# NSE2020_1.net
KiCad netlist of a schematic drawn in EAGLE
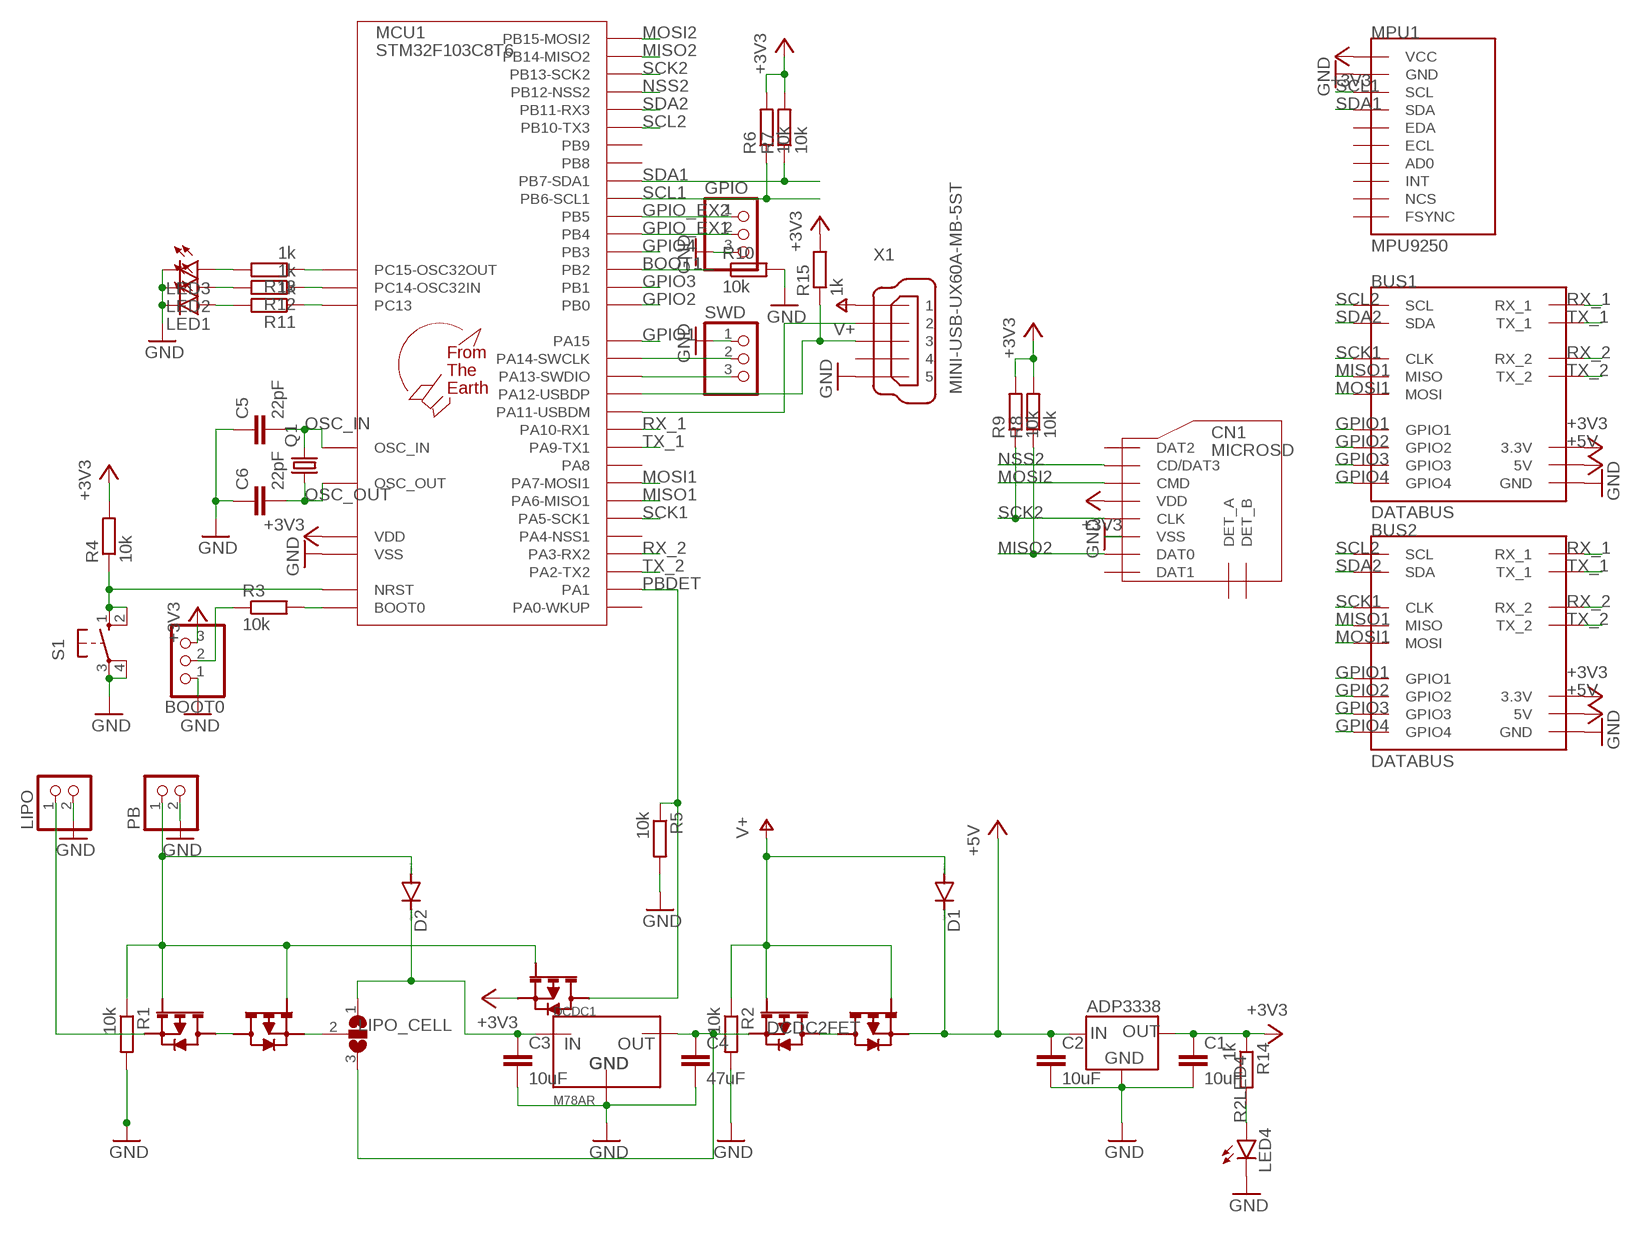
[diagram p0: schematic, sheet 1]

(export (version "E")
  (design (tool "Eeschema 10.0.6"))
  (components
    (comp (ref "BOOT0")
      (value "PINHD-1X3")
      (footprint "eagle-import:1X03")
      (libsource (lib "eagle-import") (part "PINHD-1X3"))
    )
    (comp (ref "BUS1")
      (value "DATABUS")
      (footprint "eagle-import:8X2")
      (libsource (lib "eagle-import") (part "DATABUS"))
    )
    (comp (ref "BUS2")
      (value "DATABUS")
      (footprint "eagle-import:8X2")
      (libsource (lib "eagle-import") (part "DATABUS"))
    )
    (comp (ref "C1")
      (value "10uF")
      (footprint "eagle-import:C2012")
      (libsource (lib "eagle-import") (part "C-EUC2012"))
    )
    (comp (ref "C2")
      (value "10uF")
      (footprint "eagle-import:C2012")
      (libsource (lib "eagle-import") (part "C-EUC2012"))
    )
    (comp (ref "C3")
      (value "10uF")
      (footprint "eagle-import:C2012")
      (libsource (lib "eagle-import") (part "C-EUC2012"))
    )
    (comp (ref "C4")
      (value "47uF")
      (footprint "eagle-import:C2012")
      (libsource (lib "eagle-import") (part "C-EUC2012"))
    )
    (comp (ref "C5")
      (value "22pF")
      (footprint "eagle-import:C2012")
      (libsource (lib "eagle-import") (part "C-EUC2012"))
    )
    (comp (ref "C6")
      (value "22pF")
      (footprint "eagle-import:C2012")
      (libsource (lib "eagle-import") (part "C-EUC2012"))
    )
    (comp (ref "CN1")
      (value "MICROSD")
      (footprint "eagle-import:DM3AT")
      (libsource (lib "eagle-import") (part "MICROSD"))
    )
    (comp (ref "D1")
      (value "DIODE-SOD123")
      (footprint "eagle-import:SOD123")
      (libsource (lib "eagle-import") (part "DIODE-SOD123"))
    )
    (comp (ref "D2")
      (value "DIODE-SOD123")
      (footprint "eagle-import:SOD123")
      (libsource (lib "eagle-import") (part "DIODE-SOD123"))
    )
    (comp (ref "DCDC1")
      (value "M78AR")
      (footprint "eagle-import:M78AR")
      (libsource (lib "eagle-import") (part "M78AR"))
    )
    (comp (ref "FET1")
      (value "2SJ681")
      (footprint "eagle-import:2SJ681")
      (libsource (lib "eagle-import") (part "2SJ681"))
    )
    (comp (ref "FET2")
      (value "2SJ681")
      (footprint "eagle-import:2SJ681")
      (libsource (lib "eagle-import") (part "2SJ681"))
    )
    (comp (ref "FET3")
      (value "2SJ681")
      (footprint "eagle-import:2SJ681")
      (libsource (lib "eagle-import") (part "2SJ681"))
    )
    (comp (ref "FET4")
      (value "2SJ681")
      (footprint "eagle-import:2SJ681")
      (libsource (lib "eagle-import") (part "2SJ681"))
    )
    (comp (ref "FET5")
      (value "2SJ681")
      (footprint "eagle-import:2SJ681")
      (libsource (lib "eagle-import") (part "2SJ681"))
    )
    (comp (ref "GPIO")
      (value "PINHD-1X3")
      (footprint "eagle-import:1X03")
      (libsource (lib "eagle-import") (part "PINHD-1X3"))
    )
    (comp (ref "IC1")
      (value "ADP3338-3.3")
      (footprint "eagle-import:SOT-223")
      (libsource (lib "eagle-import") (part "ADP3338-3.3"))
    )
    (comp (ref "LED1")
      (value "LEDSML0805")
      (footprint "eagle-import:SML0805")
      (libsource (lib "eagle-import") (part "LEDSML0805"))
    )
    (comp (ref "LED2")
      (value "LEDSML0805")
      (footprint "eagle-import:SML0805")
      (libsource (lib "eagle-import") (part "LEDSML0805"))
    )
    (comp (ref "LED3")
      (value "LEDSML0805")
      (footprint "eagle-import:SML0805")
      (libsource (lib "eagle-import") (part "LEDSML0805"))
    )
    (comp (ref "LED4")
      (value "LEDSML0805")
      (footprint "eagle-import:SML0805")
      (libsource (lib "eagle-import") (part "LEDSML0805"))
    )
    (comp (ref "LIPO")
      (value "PINHD-1X2")
      (footprint "eagle-import:1X02")
      (libsource (lib "eagle-import") (part "PINHD-1X2"))
    )
    (comp (ref "LIPO_CELL")
      (value "SJ2W")
      (footprint "eagle-import:SJ_2")
      (libsource (lib "eagle-import") (part "SJ2W"))
    )
    (comp (ref "MCU1")
      (value "STM32F103C8T6")
      (footprint "eagle-import:LQFP48")
      (libsource (lib "eagle-import") (part "STM32F103C8T6"))
    )
    (comp (ref "MPU1")
      (value "MPU9250")
      (footprint "eagle-import:GY-9250")
      (libsource (lib "eagle-import") (part "MPU9250"))
    )
    (comp (ref "PB")
      (value "PINHD-1X2")
      (footprint "eagle-import:1X02")
      (libsource (lib "eagle-import") (part "PINHD-1X2"))
    )
    (comp (ref "Q1")
      (value "CRYSTALHC49S")
      (footprint "eagle-import:HC49_S")
      (libsource (lib "eagle-import") (part "CRYSTALHC49S"))
    )
    (comp (ref "R1")
      (value "10k")
      (footprint "eagle-import:M2012")
      (libsource (lib "eagle-import") (part "R-EU_M2012"))
    )
    (comp (ref "R2")
      (value "10k")
      (footprint "eagle-import:M2012")
      (libsource (lib "eagle-import") (part "R-EU_M2012"))
    )
    (comp (ref "R3")
      (value "10k")
      (footprint "eagle-import:M2012")
      (libsource (lib "eagle-import") (part "R-EU_M2012"))
    )
    (comp (ref "R4")
      (value "10k")
      (footprint "eagle-import:M2012")
      (libsource (lib "eagle-import") (part "R-EU_M2012"))
    )
    (comp (ref "R5")
      (value "10k")
      (footprint "eagle-import:M2012")
      (libsource (lib "eagle-import") (part "R-EU_M2012"))
    )
    (comp (ref "R6")
      (value "10k")
      (footprint "eagle-import:M2012")
      (libsource (lib "eagle-import") (part "R-EU_M2012"))
    )
    (comp (ref "R7")
      (value "10k")
      (footprint "eagle-import:M2012")
      (libsource (lib "eagle-import") (part "R-EU_M2012"))
    )
    (comp (ref "R8")
      (value "10k")
      (footprint "eagle-import:M2012")
      (libsource (lib "eagle-import") (part "R-EU_M2012"))
    )
    (comp (ref "R9")
      (value "10k")
      (footprint "eagle-import:M2012")
      (libsource (lib "eagle-import") (part "R-EU_M2012"))
    )
    (comp (ref "R10")
      (value "10k")
      (footprint "eagle-import:M2012")
      (libsource (lib "eagle-import") (part "R-EU_M2012"))
    )
    (comp (ref "R11")
      (value "1k")
      (footprint "eagle-import:M2012")
      (libsource (lib "eagle-import") (part "R-EU_M2012"))
    )
    (comp (ref "R12")
      (value "1k")
      (footprint "eagle-import:M2012")
      (libsource (lib "eagle-import") (part "R-EU_M2012"))
    )
    (comp (ref "R13")
      (value "1k")
      (footprint "eagle-import:M2012")
      (libsource (lib "eagle-import") (part "R-EU_M2012"))
    )
    (comp (ref "R14")
      (value "1k")
      (footprint "eagle-import:M2012")
      (libsource (lib "eagle-import") (part "R-EU_M2012"))
    )
    (comp (ref "R15")
      (value "1k")
      (footprint "eagle-import:M2012")
      (libsource (lib "eagle-import") (part "R-EU_M2012"))
    )
    (comp (ref "S1")
      (value "10-XX")
      (footprint "eagle-import:B3F-10XX")
      (fields (field (name "MPN") "B3F-1000"))
      (libsource (lib "eagle-import") (part "10-XX"))
    )
    (comp (ref "SWD")
      (value "PINHD-1X3")
      (footprint "eagle-import:1X03")
      (libsource (lib "eagle-import") (part "PINHD-1X3"))
    )
    (comp (ref "U$1")
      (value "F.T.E.LOGO")
      (footprint "eagle-import:LOGO")
      (libsource (lib "eagle-import") (part "F.T.E.LOGO"))
    )
    (comp (ref "X1")
      (value "MINI-USB-UX60A-MB-5ST")
      (footprint "eagle-import:UX60A-MB-5ST")
      (libsource (lib "eagle-import") (part "MINI-USB-UX60A-MB-5ST"))
    )
  )
  (nets
    (net (code "1") (name "+3V3") (class "Default")
      (node (ref "BOOT0") (pin "3") (pinfunction "3_3") (pintype "passive"))
      (node (ref "BUS1") (pin "P6") (pinfunction "3.3V_P6") (pintype "bidirectional"))
      (node (ref "BUS2") (pin "P6") (pinfunction "3.3V_P6") (pintype "bidirectional"))
      (node (ref "C1") (pin "1") (pinfunction "1_1") (pintype "passive"))
      (node (ref "CN1") (pin "VDD") (pinfunction "VDD_VDD") (pintype "bidirectional"))
      (node (ref "FET5") (pin "P$3") (pinfunction "P$3_P$3") (pintype "bidirectional"))
      (node (ref "IC1") (pin "1") (pinfunction "OUT_1") (pintype "output"))
      (node (ref "IC1") (pin "2") (pinfunction "OUT_2") (pintype "output"))
      (node (ref "MCU1") (pin "1") (pinfunction "VDD_1") (pintype "bidirectional"))
      (node (ref "MCU1") (pin "24") (pinfunction "VDD_24") (pintype "bidirectional"))
      (node (ref "MCU1") (pin "36") (pinfunction "VDD_36") (pintype "bidirectional"))
      (node (ref "MCU1") (pin "48") (pinfunction "VDD_48") (pintype "bidirectional"))
      (node (ref "MCU1") (pin "9") (pinfunction "VDD_9") (pintype "bidirectional"))
      (node (ref "MPU1") (pin "P1") (pinfunction "VCC_P1") (pintype "bidirectional"))
      (node (ref "R14") (pin "1") (pinfunction "1_1") (pintype "passive"))
      (node (ref "R15") (pin "2") (pinfunction "2_2") (pintype "passive"))
      (node (ref "R4") (pin "2") (pinfunction "2_2") (pintype "passive"))
      (node (ref "R6") (pin "2") (pinfunction "2_2") (pintype "passive"))
      (node (ref "R7") (pin "2") (pinfunction "2_2") (pintype "passive"))
      (node (ref "R8") (pin "2") (pinfunction "2_2") (pintype "passive"))
      (node (ref "R9") (pin "2") (pinfunction "2_2") (pintype "passive"))
    )
    (net (code "2") (name "+5V") (class "Default")
      (node (ref "BUS1") (pin "P7") (pinfunction "5V_P7") (pintype "bidirectional"))
      (node (ref "BUS2") (pin "P7") (pinfunction "5V_P7") (pintype "bidirectional"))
      (node (ref "C2") (pin "1") (pinfunction "1_1") (pintype "passive"))
      (node (ref "D1") (pin "C") (pinfunction "C_C") (pintype "passive"))
      (node (ref "FET4") (pin "P$3") (pinfunction "P$3_P$3") (pintype "bidirectional"))
      (node (ref "IC1") (pin "3") (pinfunction "IN_3") (pintype "input"))
    )
    (net (code "3") (name "/BOOT1") (class "Default")
      (node (ref "MCU1") (pin "20") (pinfunction "PB2_20") (pintype "bidirectional"))
      (node (ref "R10") (pin "1") (pinfunction "1_1") (pintype "passive"))
    )
    (net (code "4") (name "/DCDC2FET") (class "Default")
      (node (ref "C4") (pin "1") (pinfunction "1_1") (pintype "passive"))
      (node (ref "DCDC1") (pin "P3") (pinfunction "OUT_P3") (pintype "bidirectional"))
      (node (ref "FET3") (pin "P$3") (pinfunction "P$3_P$3") (pintype "bidirectional"))
      (node (ref "LIPO_CELL") (pin "3") (pinfunction "3_3") (pintype "passive"))
    )
    (net (code "5") (name "/GPIO1") (class "Default")
      (node (ref "BUS1") (pin "P3") (pinfunction "GPIO1_P3") (pintype "bidirectional"))
      (node (ref "BUS2") (pin "P3") (pinfunction "GPIO1_P3") (pintype "bidirectional"))
      (node (ref "MCU1") (pin "38") (pinfunction "PA15_38") (pintype "bidirectional"))
    )
    (net (code "6") (name "/GPIO2") (class "Default")
      (node (ref "BUS1") (pin "P10") (pinfunction "GPIO2_P10") (pintype "bidirectional"))
      (node (ref "BUS2") (pin "P10") (pinfunction "GPIO2_P10") (pintype "bidirectional"))
      (node (ref "MCU1") (pin "18") (pinfunction "PB0_18") (pintype "bidirectional"))
    )
    (net (code "7") (name "/GPIO3") (class "Default")
      (node (ref "BUS1") (pin "P14") (pinfunction "GPIO3_P14") (pintype "bidirectional"))
      (node (ref "BUS2") (pin "P14") (pinfunction "GPIO3_P14") (pintype "bidirectional"))
      (node (ref "MCU1") (pin "19") (pinfunction "PB1_19") (pintype "bidirectional"))
    )
    (net (code "8") (name "/GPIO4") (class "Default")
      (node (ref "BUS1") (pin "P15") (pinfunction "GPIO4_P15") (pintype "bidirectional"))
      (node (ref "BUS2") (pin "P15") (pinfunction "GPIO4_P15") (pintype "bidirectional"))
      (node (ref "MCU1") (pin "39") (pinfunction "PB3_39") (pintype "bidirectional"))
    )
    (net (code "9") (name "/GPIO_EX1") (class "Default")
      (node (ref "GPIO") (pin "2") (pinfunction "2_2") (pintype "passive"))
      (node (ref "MCU1") (pin "40") (pinfunction "PB4_40") (pintype "bidirectional"))
    )
    (net (code "10") (name "/GPIO_EX2") (class "Default")
      (node (ref "GPIO") (pin "1") (pinfunction "1_1") (pintype "passive"))
      (node (ref "MCU1") (pin "41") (pinfunction "PB5_41") (pintype "bidirectional"))
    )
    (net (code "11") (name "/MISO1") (class "Default")
      (node (ref "BUS1") (pin "P12") (pinfunction "MISO_P12") (pintype "bidirectional"))
      (node (ref "BUS2") (pin "P12") (pinfunction "MISO_P12") (pintype "bidirectional"))
      (node (ref "MCU1") (pin "16") (pinfunction "PA6-MISO1_16") (pintype "bidirectional"))
    )
    (net (code "12") (name "/MISO2") (class "Default")
      (node (ref "CN1") (pin "DAT0") (pinfunction "DAT0_DAT0") (pintype "bidirectional"))
      (node (ref "MCU1") (pin "27") (pinfunction "PB14-MISO2_27") (pintype "bidirectional"))
      (node (ref "R8") (pin "1") (pinfunction "1_1") (pintype "passive"))
    )
    (net (code "13") (name "/MOSI1") (class "Default")
      (node (ref "BUS1") (pin "P2") (pinfunction "MOSI_P2") (pintype "bidirectional"))
      (node (ref "BUS2") (pin "P2") (pinfunction "MOSI_P2") (pintype "bidirectional"))
      (node (ref "MCU1") (pin "17") (pinfunction "PA7-MOSI1_17") (pintype "bidirectional"))
    )
    (net (code "14") (name "/MOSI2") (class "Default")
      (node (ref "CN1") (pin "CMD") (pinfunction "CMD_CMD") (pintype "bidirectional"))
      (node (ref "MCU1") (pin "28") (pinfunction "PB15-MOSI2_28") (pintype "bidirectional"))
    )
    (net (code "15") (name "/NSS2") (class "Default")
      (node (ref "CN1") (pin "CD/DAT3") (pinfunction "CD/DAT3_CD/DAT3") (pintype "bidirectional"))
      (node (ref "MCU1") (pin "25") (pinfunction "PB12-NSS2_25") (pintype "bidirectional"))
    )
    (net (code "16") (name "/OSC_IN") (class "Default")
      (node (ref "C5") (pin "2") (pinfunction "2_2") (pintype "passive"))
      (node (ref "MCU1") (pin "5") (pinfunction "OSC_IN_5") (pintype "bidirectional"))
      (node (ref "Q1") (pin "2") (pinfunction "2_2") (pintype "passive"))
    )
    (net (code "17") (name "/OSC_OUT") (class "Default")
      (node (ref "C6") (pin "2") (pinfunction "2_2") (pintype "passive"))
      (node (ref "MCU1") (pin "6") (pinfunction "OSC_OUT_6") (pintype "bidirectional"))
      (node (ref "Q1") (pin "1") (pinfunction "1_1") (pintype "passive"))
    )
    (net (code "18") (name "/PBDET") (class "Default")
      (node (ref "FET5") (pin "P$2") (pinfunction "P$1_P$2") (pintype "bidirectional"))
      (node (ref "FET5") (pin "P$4") (pinfunction "P$1_P$4") (pintype "bidirectional"))
      (node (ref "MCU1") (pin "11") (pinfunction "PA1_11") (pintype "bidirectional"))
      (node (ref "R5") (pin "1") (pinfunction "1_1") (pintype "passive"))
    )
    (net (code "19") (name "/R2LED4") (class "Default")
      (node (ref "LED4") (pin "A") (pinfunction "A_A") (pintype "passive"))
      (node (ref "R14") (pin "2") (pinfunction "2_2") (pintype "passive"))
    )
    (net (code "20") (name "/RX_1") (class "Default")
      (node (ref "BUS1") (pin "P4") (pinfunction "RX_1_P4") (pintype "bidirectional"))
      (node (ref "BUS2") (pin "P4") (pinfunction "RX_1_P4") (pintype "bidirectional"))
      (node (ref "MCU1") (pin "31") (pinfunction "PA10-RX1_31") (pintype "bidirectional"))
    )
    (net (code "21") (name "/RX_2") (class "Default")
      (node (ref "BUS1") (pin "P9") (pinfunction "RX_2_P9") (pintype "bidirectional"))
      (node (ref "BUS2") (pin "P9") (pinfunction "RX_2_P9") (pintype "bidirectional"))
      (node (ref "MCU1") (pin "13") (pinfunction "PA3-RX2_13") (pintype "bidirectional"))
    )
    (net (code "22") (name "/SCK1") (class "Default")
      (node (ref "BUS1") (pin "P1") (pinfunction "CLK_P1") (pintype "bidirectional"))
      (node (ref "BUS2") (pin "P1") (pinfunction "CLK_P1") (pintype "bidirectional"))
      (node (ref "MCU1") (pin "15") (pinfunction "PA5-SCK1_15") (pintype "bidirectional"))
    )
    (net (code "23") (name "/SCK2") (class "Default")
      (node (ref "CN1") (pin "CLK") (pinfunction "CLK_CLK") (pintype "bidirectional"))
      (node (ref "MCU1") (pin "26") (pinfunction "PB13-SCK2_26") (pintype "bidirectional"))
      (node (ref "R9") (pin "1") (pinfunction "1_1") (pintype "passive"))
    )
    (net (code "24") (name "/SCL1") (class "Default")
      (node (ref "MCU1") (pin "42") (pinfunction "PB6-SCL1_42") (pintype "bidirectional"))
      (node (ref "MPU1") (pin "P3") (pinfunction "SCL_P3") (pintype "bidirectional"))
      (node (ref "R6") (pin "1") (pinfunction "1_1") (pintype "passive"))
    )
    (net (code "25") (name "/SCL2") (class "Default")
      (node (ref "BUS1") (pin "P0") (pinfunction "SCL_P0") (pintype "bidirectional"))
      (node (ref "BUS2") (pin "P0") (pinfunction "SCL_P0") (pintype "bidirectional"))
      (node (ref "MCU1") (pin "21") (pinfunction "PB10-TX3_21") (pintype "bidirectional"))
    )
    (net (code "26") (name "/SDA1") (class "Default")
      (node (ref "MCU1") (pin "43") (pinfunction "PB7-SDA1_43") (pintype "bidirectional"))
      (node (ref "MPU1") (pin "P4") (pinfunction "SDA_P4") (pintype "bidirectional"))
      (node (ref "R7") (pin "1") (pinfunction "1_1") (pintype "passive"))
    )
    (net (code "27") (name "/SDA2") (class "Default")
      (node (ref "BUS1") (pin "P13") (pinfunction "SDA_P13") (pintype "bidirectional"))
      (node (ref "BUS2") (pin "P13") (pinfunction "SDA_P13") (pintype "bidirectional"))
      (node (ref "MCU1") (pin "22") (pinfunction "PB11-RX3_22") (pintype "bidirectional"))
    )
    (net (code "28") (name "/TX_1") (class "Default")
      (node (ref "BUS1") (pin "P5") (pinfunction "TX_1_P5") (pintype "bidirectional"))
      (node (ref "BUS2") (pin "P5") (pinfunction "TX_1_P5") (pintype "bidirectional"))
      (node (ref "MCU1") (pin "30") (pinfunction "PA9-TX1_30") (pintype "bidirectional"))
    )
    (net (code "29") (name "/TX_2") (class "Default")
      (node (ref "BUS1") (pin "P8") (pinfunction "TX_2_P8") (pintype "bidirectional"))
      (node (ref "BUS2") (pin "P8") (pinfunction "TX_2_P8") (pintype "bidirectional"))
      (node (ref "MCU1") (pin "12") (pinfunction "PA2-TX2_12") (pintype "bidirectional"))
    )
    (net (code "30") (name "GND") (class "Default")
      (node (ref "BOOT0") (pin "1") (pinfunction "1_1") (pintype "passive"))
      (node (ref "BUS1") (pin "P11") (pinfunction "GND_P11") (pintype "bidirectional"))
      (node (ref "BUS2") (pin "P11") (pinfunction "GND_P11") (pintype "bidirectional"))
      (node (ref "C1") (pin "2") (pinfunction "2_2") (pintype "passive"))
      (node (ref "C2") (pin "2") (pinfunction "2_2") (pintype "passive"))
      (node (ref "C3") (pin "2") (pinfunction "2_2") (pintype "passive"))
      (node (ref "C4") (pin "2") (pinfunction "2_2") (pintype "passive"))
      (node (ref "C5") (pin "1") (pinfunction "1_1") (pintype "passive"))
      (node (ref "C6") (pin "1") (pinfunction "1_1") (pintype "passive"))
      (node (ref "CN1") (pin "VSS") (pinfunction "VSS_VSS") (pintype "bidirectional"))
      (node (ref "DCDC1") (pin "P2") (pinfunction "GND_P2") (pintype "bidirectional"))
      (node (ref "GPIO") (pin "3") (pinfunction "3_3") (pintype "passive"))
      (node (ref "IC1") (pin "4") (pinfunction "GND_4") (pintype "bidirectional"))
      (node (ref "LED1") (pin "C") (pinfunction "C_C") (pintype "passive"))
      (node (ref "LED2") (pin "C") (pinfunction "C_C") (pintype "passive"))
      (node (ref "LED3") (pin "C") (pinfunction "C_C") (pintype "passive"))
      (node (ref "LED4") (pin "C") (pinfunction "C_C") (pintype "passive"))
      (node (ref "LIPO") (pin "2") (pinfunction "2_2") (pintype "passive"))
      (node (ref "MCU1") (pin "23") (pinfunction "VSS_23") (pintype "bidirectional"))
      (node (ref "MCU1") (pin "35") (pinfunction "VSS_35") (pintype "bidirectional"))
      (node (ref "MCU1") (pin "47") (pinfunction "VSS_47") (pintype "bidirectional"))
      (node (ref "MCU1") (pin "8") (pinfunction "VSS_8") (pintype "bidirectional"))
      (node (ref "MPU1") (pin "P2") (pinfunction "GND_P2") (pintype "bidirectional"))
      (node (ref "PB") (pin "2") (pinfunction "2_2") (pintype "passive"))
      (node (ref "R1") (pin "2") (pinfunction "2_2") (pintype "passive"))
      (node (ref "R10") (pin "2") (pinfunction "2_2") (pintype "passive"))
      (node (ref "R2") (pin "2") (pinfunction "2_2") (pintype "passive"))
      (node (ref "R5") (pin "2") (pinfunction "2_2") (pintype "passive"))
      (node (ref "S1") (pin "3") (pinfunction "P_3") (pintype "passive"))
      (node (ref "S1") (pin "4") (pinfunction "P1_4") (pintype "passive"))
      (node (ref "SWD") (pin "1") (pinfunction "1_1") (pintype "passive"))
      (node (ref "X1") (pin "5") (pinfunction "5_5") (pintype "input"))
    )
    (net (code "31") (name "Net-(BOOT0-Pad2)") (class "Default")
      (node (ref "BOOT0") (pin "2") (pinfunction "2_2") (pintype "passive"))
      (node (ref "R3") (pin "1") (pinfunction "1_1") (pintype "passive"))
    )
    (net (code "32") (name "Net-(DCDC1-IN)") (class "Default")
      (node (ref "C3") (pin "1") (pinfunction "1_1") (pintype "passive"))
      (node (ref "D2") (pin "C") (pinfunction "C_C") (pintype "passive"))
      (node (ref "DCDC1") (pin "P1") (pinfunction "IN_P1") (pintype "bidirectional"))
      (node (ref "LIPO_CELL") (pin "1") (pinfunction "1_1") (pintype "passive"))
    )
    (net (code "33") (name "Net-(FET1-P$1-PadP$2)") (class "Default")
      (node (ref "FET1") (pin "P$2") (pinfunction "P$1_P$2") (pintype "bidirectional"))
      (node (ref "FET1") (pin "P$4") (pinfunction "P$1_P$4") (pintype "bidirectional"))
      (node (ref "FET2") (pin "P$2") (pinfunction "P$1_P$2") (pintype "bidirectional"))
      (node (ref "FET2") (pin "P$4") (pinfunction "P$1_P$4") (pintype "bidirectional"))
    )
    (net (code "34") (name "Net-(FET1-P$2)") (class "Default")
      (node (ref "D2") (pin "A") (pinfunction "A_A") (pintype "passive"))
      (node (ref "FET1") (pin "P$1") (pinfunction "P$2_P$1") (pintype "bidirectional"))
      (node (ref "FET2") (pin "P$1") (pinfunction "P$2_P$1") (pintype "bidirectional"))
      (node (ref "FET5") (pin "P$1") (pinfunction "P$2_P$1") (pintype "bidirectional"))
      (node (ref "PB") (pin "1") (pinfunction "1_1") (pintype "passive"))
      (node (ref "R1") (pin "1") (pinfunction "1_1") (pintype "passive"))
    )
    (net (code "35") (name "Net-(FET1-PadP$3)") (class "Default")
      (node (ref "FET1") (pin "P$3") (pinfunction "P$3_P$3") (pintype "bidirectional"))
      (node (ref "LIPO") (pin "1") (pinfunction "1_1") (pintype "passive"))
    )
    (net (code "36") (name "Net-(FET2-PadP$3)") (class "Default")
      (node (ref "FET2") (pin "P$3") (pinfunction "P$3_P$3") (pintype "bidirectional"))
      (node (ref "LIPO_CELL") (pin "2") (pinfunction "2_2") (pintype "passive"))
    )
    (net (code "37") (name "Net-(FET3-P$1-PadP$2)") (class "Default")
      (node (ref "FET3") (pin "P$2") (pinfunction "P$1_P$2") (pintype "bidirectional"))
      (node (ref "FET3") (pin "P$4") (pinfunction "P$1_P$4") (pintype "bidirectional"))
      (node (ref "FET4") (pin "P$2") (pinfunction "P$1_P$2") (pintype "bidirectional"))
      (node (ref "FET4") (pin "P$4") (pinfunction "P$1_P$4") (pintype "bidirectional"))
    )
    (net (code "38") (name "Net-(LED1-PadA)") (class "Default")
      (node (ref "LED1") (pin "A") (pinfunction "A_A") (pintype "passive"))
      (node (ref "R11") (pin "2") (pinfunction "2_2") (pintype "passive"))
    )
    (net (code "39") (name "Net-(LED2-PadA)") (class "Default")
      (node (ref "LED2") (pin "A") (pinfunction "A_A") (pintype "passive"))
      (node (ref "R12") (pin "2") (pinfunction "2_2") (pintype "passive"))
    )
    (net (code "40") (name "Net-(LED3-PadA)") (class "Default")
      (node (ref "LED3") (pin "A") (pinfunction "A_A") (pintype "passive"))
      (node (ref "R13") (pin "2") (pinfunction "2_2") (pintype "passive"))
    )
    (net (code "41") (name "Net-(MCU1-BOOT0)") (class "Default")
      (node (ref "MCU1") (pin "44") (pinfunction "BOOT0_44") (pintype "bidirectional"))
      (node (ref "R3") (pin "2") (pinfunction "2_2") (pintype "passive"))
    )
    (net (code "42") (name "Net-(MCU1-NRST)") (class "Default")
      (node (ref "MCU1") (pin "7") (pinfunction "NRST_7") (pintype "bidirectional"))
      (node (ref "R4") (pin "1") (pinfunction "1_1") (pintype "passive"))
      (node (ref "S1") (pin "1") (pinfunction "S_1") (pintype "passive"))
      (node (ref "S1") (pin "2") (pinfunction "S1_2") (pintype "passive"))
    )
    (net (code "43") (name "Net-(MCU1-PA11-USBDM)") (class "Default")
      (node (ref "MCU1") (pin "32") (pinfunction "PA11-USBDM_32") (pintype "bidirectional"))
      (node (ref "X1") (pin "2") (pinfunction "2_2") (pintype "input"))
    )
    (net (code "44") (name "Net-(MCU1-PA12-USBDP)") (class "Default")
      (node (ref "MCU1") (pin "33") (pinfunction "PA12-USBDP_33") (pintype "bidirectional"))
      (node (ref "R15") (pin "1") (pinfunction "1_1") (pintype "passive"))
      (node (ref "X1") (pin "3") (pinfunction "3_3") (pintype "input"))
    )
    (net (code "45") (name "Net-(MCU1-PA13-SWDIO)") (class "Default")
      (node (ref "MCU1") (pin "34") (pinfunction "PA13-SWDIO_34") (pintype "bidirectional"))
      (node (ref "SWD") (pin "3") (pinfunction "3_3") (pintype "passive"))
    )
    (net (code "46") (name "Net-(MCU1-PA14-SWCLK)") (class "Default")
      (node (ref "MCU1") (pin "37") (pinfunction "PA14-SWCLK_37") (pintype "bidirectional"))
      (node (ref "SWD") (pin "2") (pinfunction "2_2") (pintype "passive"))
    )
    (net (code "47") (name "Net-(MCU1-PC13)") (class "Default")
      (node (ref "MCU1") (pin "2") (pinfunction "PC13_2") (pintype "bidirectional"))
      (node (ref "R11") (pin "1") (pinfunction "1_1") (pintype "passive"))
    )
    (net (code "48") (name "Net-(MCU1-PC14-OSC32IN)") (class "Default")
      (node (ref "MCU1") (pin "3") (pinfunction "PC14-OSC32IN_3") (pintype "bidirectional"))
      (node (ref "R12") (pin "1") (pinfunction "1_1") (pintype "passive"))
    )
    (net (code "49") (name "Net-(MCU1-PC15-OSC32OUT)") (class "Default")
      (node (ref "MCU1") (pin "4") (pinfunction "PC15-OSC32OUT_4") (pintype "bidirectional"))
      (node (ref "R13") (pin "1") (pinfunction "1_1") (pintype "passive"))
    )
    (net (code "50") (name "V+") (class "Default")
      (node (ref "D1") (pin "A") (pinfunction "A_A") (pintype "passive"))
      (node (ref "FET3") (pin "P$1") (pinfunction "P$2_P$1") (pintype "bidirectional"))
      (node (ref "FET4") (pin "P$1") (pinfunction "P$2_P$1") (pintype "bidirectional"))
      (node (ref "R2") (pin "1") (pinfunction "1_1") (pintype "passive"))
      (node (ref "X1") (pin "1") (pinfunction "1_1") (pintype "input"))
    )
    (net (code "51") (name "unconnected-(CN1-PadDAT1)") (class "Default")
      (node (ref "CN1") (pin "DAT1") (pinfunction "DAT1_DAT1") (pintype "bidirectional"))
    )
    (net (code "52") (name "unconnected-(CN1-PadDAT2)") (class "Default")
      (node (ref "CN1") (pin "DAT2") (pinfunction "DAT2_DAT2") (pintype "bidirectional"))
    )
    (net (code "53") (name "unconnected-(CN1-PadDET_A)") (class "Default")
      (node (ref "CN1") (pin "DET_A") (pinfunction "DET_A_DET_A") (pintype "bidirectional"))
    )
    (net (code "54") (name "unconnected-(CN1-PadDET_B)") (class "Default")
      (node (ref "CN1") (pin "DET_B") (pinfunction "DET_B_DET_B") (pintype "bidirectional"))
    )
    (net (code "55") (name "unconnected-(MCU1-PA0-WKUP-Pad10)") (class "Default")
      (node (ref "MCU1") (pin "10") (pinfunction "PA0-WKUP_10") (pintype "bidirectional"))
    )
    (net (code "56") (name "unconnected-(MCU1-PA4-NSS1-Pad14)") (class "Default")
      (node (ref "MCU1") (pin "14") (pinfunction "PA4-NSS1_14") (pintype "bidirectional"))
    )
    (net (code "57") (name "unconnected-(MCU1-PA8-Pad29)") (class "Default")
      (node (ref "MCU1") (pin "29") (pinfunction "PA8_29") (pintype "bidirectional"))
    )
    (net (code "58") (name "unconnected-(MCU1-PB8-Pad45)") (class "Default")
      (node (ref "MCU1") (pin "45") (pinfunction "PB8_45") (pintype "bidirectional"))
    )
    (net (code "59") (name "unconnected-(MCU1-PB9-Pad46)") (class "Default")
      (node (ref "MCU1") (pin "46") (pinfunction "PB9_46") (pintype "bidirectional"))
    )
    (net (code "60") (name "unconnected-(MPU1-AD0-PadP7)") (class "Default")
      (node (ref "MPU1") (pin "P7") (pinfunction "AD0_P7") (pintype "bidirectional"))
    )
    (net (code "61") (name "unconnected-(MPU1-ECL-PadP6)") (class "Default")
      (node (ref "MPU1") (pin "P6") (pinfunction "ECL_P6") (pintype "bidirectional"))
    )
    (net (code "62") (name "unconnected-(MPU1-EDA-PadP5)") (class "Default")
      (node (ref "MPU1") (pin "P5") (pinfunction "EDA_P5") (pintype "bidirectional"))
    )
    (net (code "63") (name "unconnected-(MPU1-FSYNC-PadP10)") (class "Default")
      (node (ref "MPU1") (pin "P10") (pinfunction "FSYNC_P10") (pintype "bidirectional"))
    )
    (net (code "64") (name "unconnected-(MPU1-INT-PadP8)") (class "Default")
      (node (ref "MPU1") (pin "P8") (pinfunction "INT_P8") (pintype "bidirectional"))
    )
    (net (code "65") (name "unconnected-(MPU1-NCS-PadP9)") (class "Default")
      (node (ref "MPU1") (pin "P9") (pinfunction "NCS_P9") (pintype "bidirectional"))
    )
    (net (code "66") (name "unconnected-(X1-Pad4)") (class "Default")
      (node (ref "X1") (pin "4") (pinfunction "4_4") (pintype "input"))
    )
  )
)
